# esphaptc.net
KiCad netlist of a schematic drawn in EasyEDA
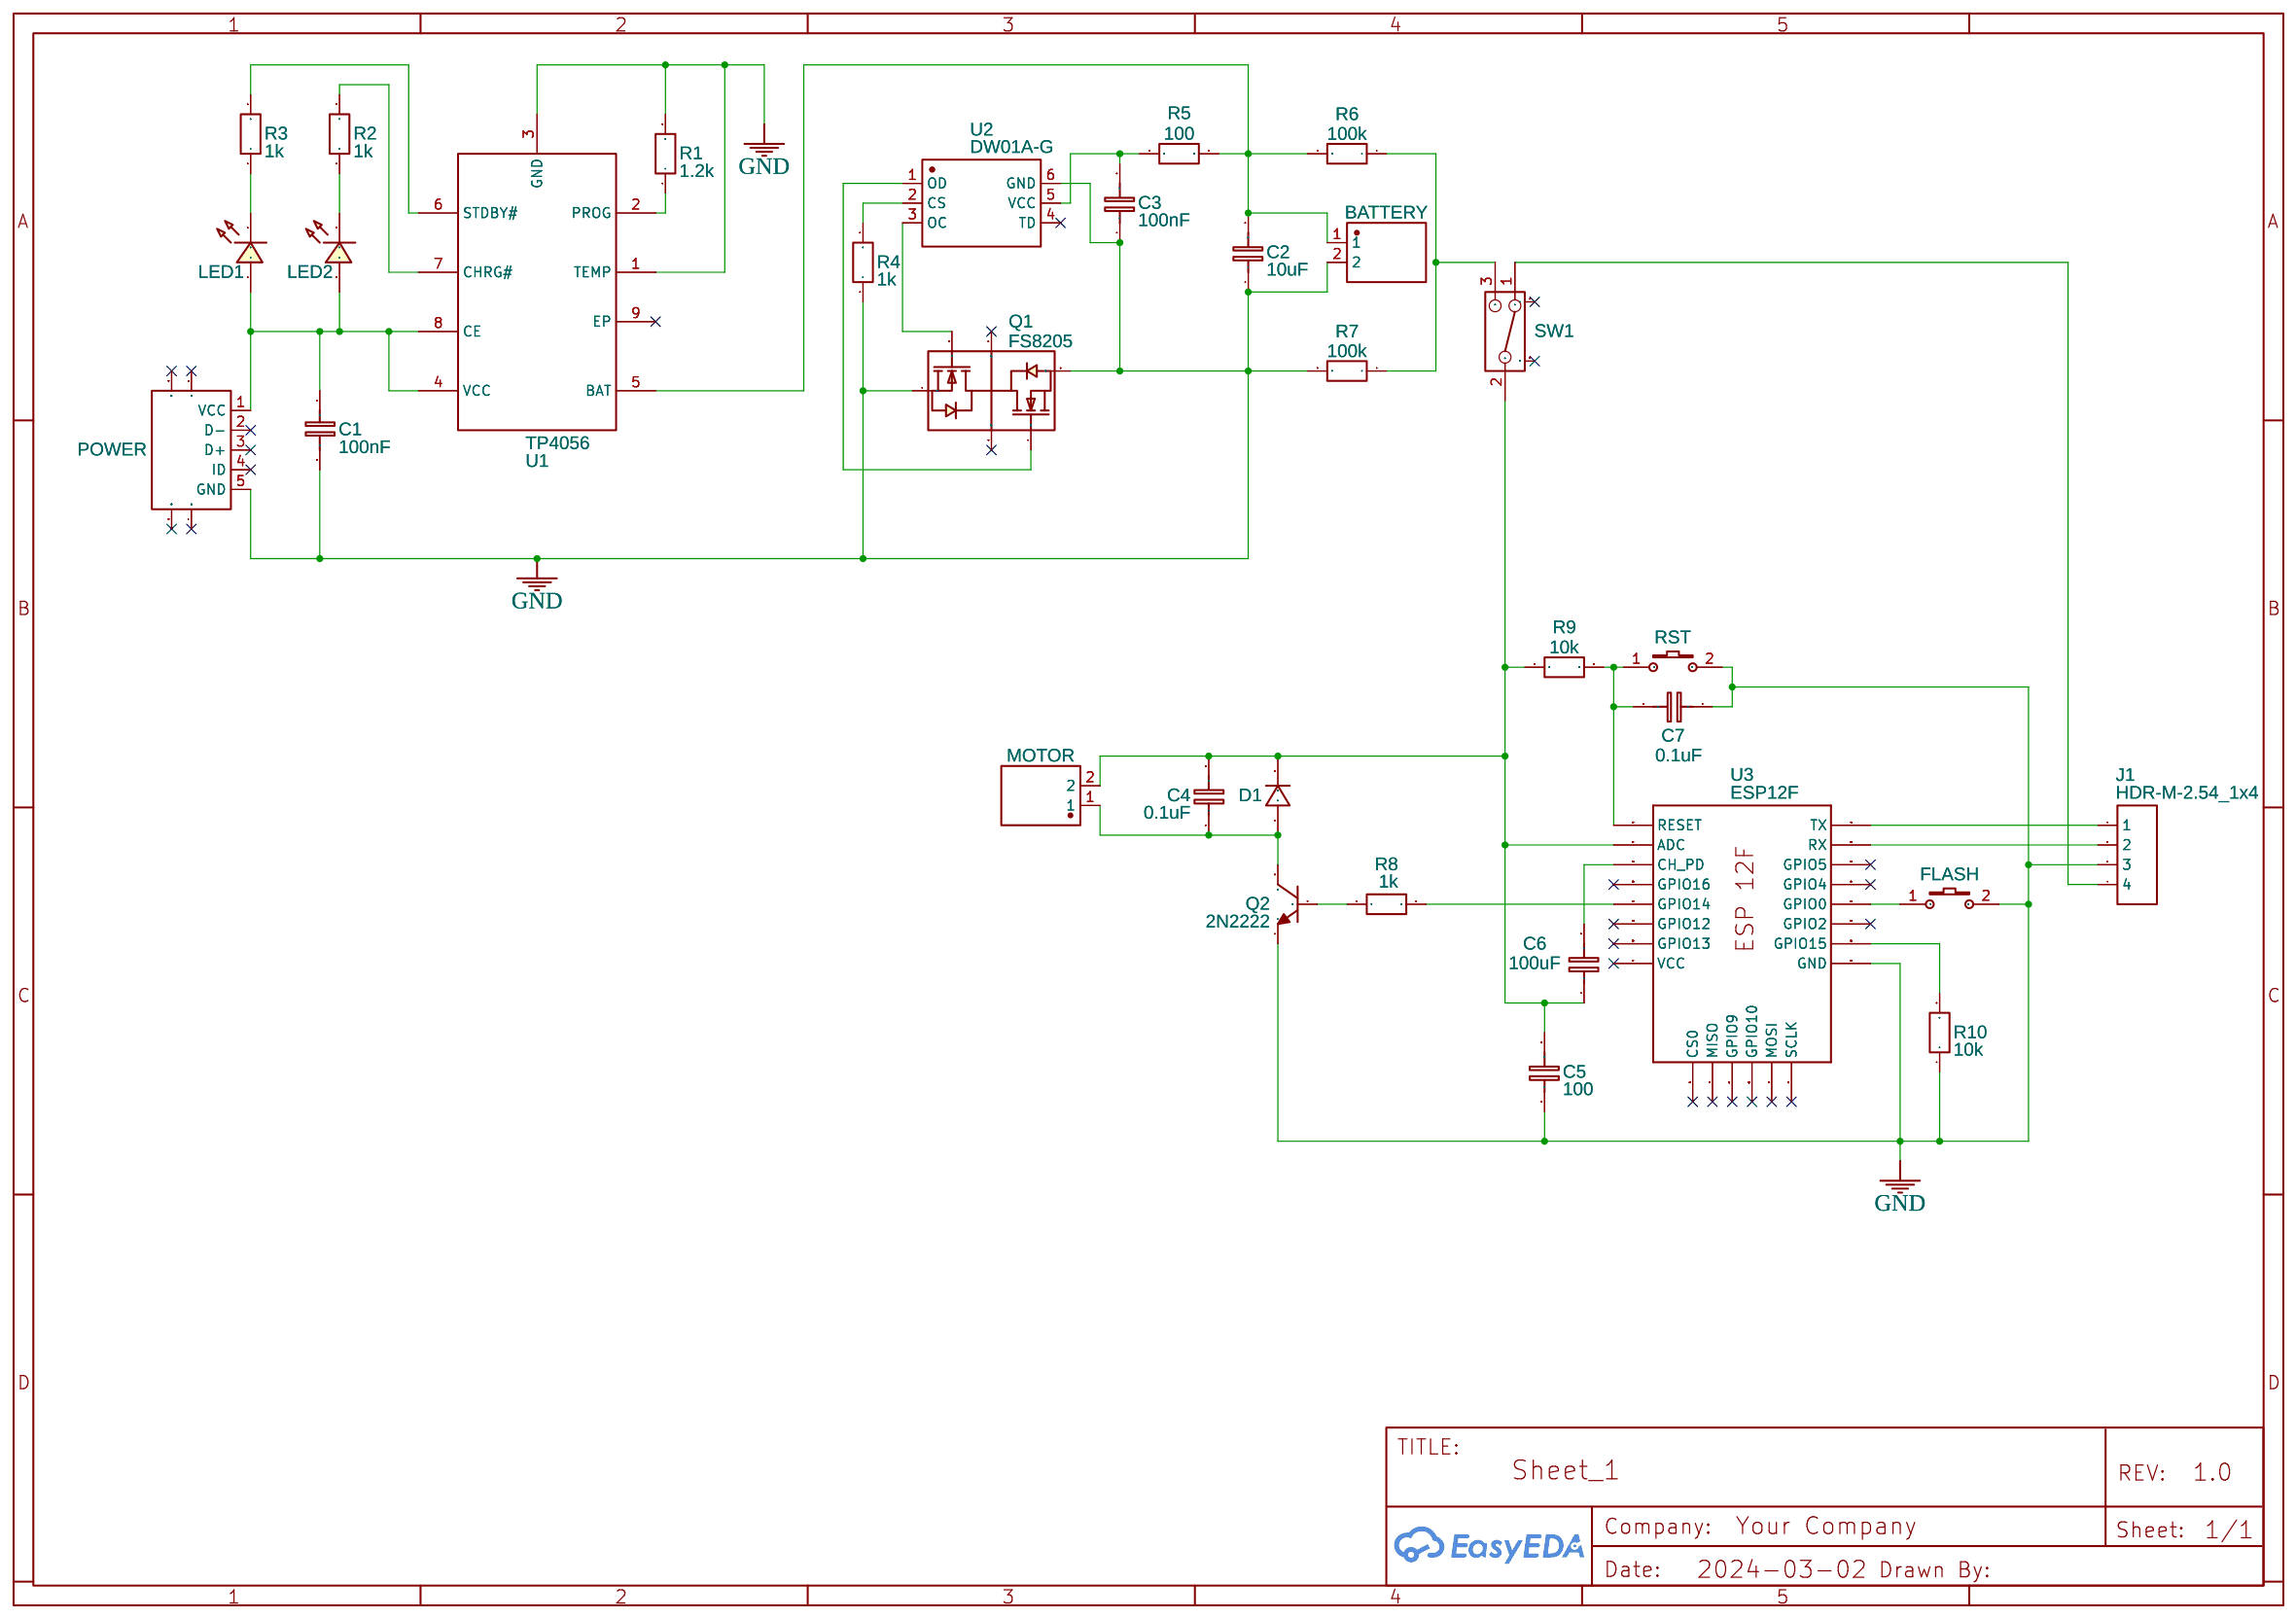
[diagram p0: schematic sheet]

(export (version "E")
  (design (tool "Eeschema 10.0.6"))
  (components
    (comp (ref "BATTERY")
      (value "B02B-XASK-1-A(LF)(SN)")
      (fields (field (name "Manufacturer") "JST"))
      (libsource (lib "") (part "B02B-XASK-1-A(LF)(SN)_1"))
    )
    (comp (ref "C1") (value "100nF") (libsource (lib "") (part "C_0603_EU_2")))
    (comp (ref "C2") (value "10uF") (libsource (lib "") (part "C_0603_EU_3")))
    (comp (ref "C3") (value "100nF") (libsource (lib "") (part "C_0603_EU_3")))
    (comp (ref "C4") (value "0.1uF") (libsource (lib "") (part "C_0603_EU_1")))
    (comp (ref "C5") (value "100") (libsource (lib "") (part "C_0603_EU")))
    (comp (ref "C6") (value "100uF") (libsource (lib "") (part "C_0603_EU")))
    (comp (ref "C7") (value "0.1uF") (libsource (lib "") (part "C_0603_EU_4")))
    (comp (ref "D1")
      (value "1N4007W")
      (fields (field (name "Manufacturer") "BLUE ROCKET"))
      (libsource (lib "") (part "1N4007W"))
    )
    (comp (ref "FLASH")
      (value "K2-3.6×6.1_SMD")
      (fields (field (name "Manufacturer Part") "K2-1107ST-A4SW-06"))
      (libsource (lib "") (part "K2-3.6×6.1_SMD"))
    )
    (comp (ref "J1") (value "HDR-M-2.54_1x4") (libsource (lib "") (part "HDR-M-2.54_1x4")))
    (comp (ref "LED1")
      (value "LED-0603_R")
      (fields
        (field (name "Manufacturer Part") "19-217/R6C-AL1M2VY/3T")
        (field (name "Manufacturer") "EVERLIGHT(台湾亿光)")
      )
      (libsource (lib "") (part "LED-0603_R"))
    )
    (comp (ref "LED2")
      (value "LED-0603_B")
      (fields
        (field (name "Manufacturer Part") "19-217/BHC-ZL1M2RY/3T")
        (field (name "Manufacturer") "EVERLIGHT(台湾亿光)")
      )
      (libsource (lib "") (part "LED-0603_B"))
    )
    (comp (ref "MOTOR")
      (value "B02B-XASK-1-A(LF)(SN)")
      (fields (field (name "Manufacturer") "JST"))
      (libsource (lib "") (part "B02B-XASK-1-A(LF)(SN)"))
    )
    (comp (ref "POWER")
      (value "USB-Micro_2")
      (fields (field (name "Manufacturer") "ValuePro"))
      (libsource (lib "") (part "USB-Micro_2"))
    )
    (comp (ref "Q1")
      (value "FS8205")
      (fields (field (name "Manufacturer") "FORTUNE(富晶)"))
      (libsource (lib "") (part "FS8205"))
    )
    (comp (ref "Q2")
      (value "2N2222")
      (fields (field (name "Manufacturer Part") "2n3904S-RTK/PS") (field (name "Manufacturer") "KEC"))
      (libsource (lib "") (part "2N3904(SOT-23)"))
    )
    (comp (ref "R1") (value "1.2k") (libsource (lib "") (part "R_0603_EU_2")))
    (comp (ref "R2") (value "1k") (libsource (lib "") (part "R_0603_EU_2")))
    (comp (ref "R3") (value "1k") (libsource (lib "") (part "R_0603_EU_2")))
    (comp (ref "R4") (value "1k") (libsource (lib "") (part "R_0603_EU_2")))
    (comp (ref "R5") (value "100") (libsource (lib "") (part "R_0603_EU_1")))
    (comp (ref "R6") (value "100k") (libsource (lib "") (part "R_0603_EU")))
    (comp (ref "R7") (value "100k") (libsource (lib "") (part "R_0603_EU")))
    (comp (ref "R8") (value "1k") (libsource (lib "") (part "R_0603_EU")))
    (comp (ref "R9") (value "10k") (libsource (lib "") (part "R_0603_EU_1")))
    (comp (ref "R10") (value "10k") (libsource (lib "") (part "R_0603_EU_2")))
    (comp (ref "RST")
      (value "K2-3.6×6.1_SMD")
      (fields (field (name "Manufacturer Part") "K2-1107ST-A4SW-06"))
      (libsource (lib "") (part "K2-3.6×6.1_SMD_1"))
    )
    (comp (ref "SW1")
      (value "SK-12D02-VG5")
      (fields (field (name "Manufacturer") "Rectangular Connectors - Contacts"))
      (libsource (lib "") (part "SK-12D02-VG5"))
    )
    (comp (ref "U1")
      (value "TP4056")
      (fields
        (field (name "Manufacturer Part") "TP4056-42-ESOP8")
        (field (name "Manufacturer") "TOPPOWER(南京拓微)")
      )
      (libsource (lib "") (part "TP4056"))
    )
    (comp (ref "U2")
      (value "DW01A-G")
      (fields (field (name "Manufacturer") "FORTUNE(富晶)"))
      (libsource (lib "") (part "DW01A-G"))
    )
    (comp (ref "U3") (value "ESP12F") (libsource (lib "") (part "ESP12F")))
  )
  (nets
    (net (code "1") (name "GND") (class "Default")
      (node (ref "BATTERY") (pin "2") (pinfunction "2_2") (pintype "unspecified"))
      (node (ref "C1") (pin "2") (pinfunction "2_2") (pintype "unspecified"))
      (node (ref "C2") (pin "1") (pinfunction "1_1") (pintype "unspecified"))
      (node (ref "C3") (pin "1") (pinfunction "1_1") (pintype "unspecified"))
      (node (ref "C5") (pin "1") (pinfunction "1_1") (pintype "unspecified"))
      (node (ref "C7") (pin "1") (pinfunction "1_1") (pintype "unspecified"))
      (node (ref "FLASH") (pin "2") (pinfunction "2_2") (pintype "unspecified"))
      (node (ref "J1") (pin "3") (pinfunction "3_3") (pintype "unspecified"))
      (node (ref "POWER") (pin "5") (pinfunction "GND_5") (pintype "input"))
      (node (ref "Q1") (pin "1") (pinfunction "S1_1") (pintype "unspecified"))
      (node (ref "Q1") (pin "3") (pinfunction "S2_3") (pintype "unspecified"))
      (node (ref "Q2") (pin "1") (pinfunction "E_1") (pintype "input"))
      (node (ref "R1") (pin "2") (pinfunction "2_2") (pintype "unspecified"))
      (node (ref "R10") (pin "1") (pinfunction "1_1") (pintype "unspecified"))
      (node (ref "R4") (pin "1") (pinfunction "1_1") (pintype "unspecified"))
      (node (ref "R7") (pin "2") (pinfunction "2_2") (pintype "unspecified"))
      (node (ref "RST") (pin "2") (pinfunction "2_2") (pintype "unspecified"))
      (node (ref "U1") (pin "1") (pinfunction "TEMP_1") (pintype "unspecified"))
      (node (ref "U1") (pin "3") (pinfunction "GND_3") (pintype "unspecified"))
      (node (ref "U2") (pin "6") (pinfunction "GND_6") (pintype "unspecified"))
      (node (ref "U3") (pin "GND") (pinfunction "GND_GND") (pintype "bidirectional"))
    )
    (net (code "2") (name "Net-(C4-Pad2)") (class "Default")
      (node (ref "C4") (pin "2") (pinfunction "2_2") (pintype "unspecified"))
      (node (ref "C5") (pin "2") (pinfunction "2_2") (pintype "unspecified"))
      (node (ref "C6") (pin "1") (pinfunction "1_1") (pintype "unspecified"))
      (node (ref "D1") (pin "1") (pinfunction "1_1") (pintype "unspecified"))
      (node (ref "MOTOR") (pin "2") (pinfunction "2_2") (pintype "unspecified"))
      (node (ref "R9") (pin "1") (pinfunction "1_1") (pintype "unspecified"))
      (node (ref "SW1") (pin "2") (pinfunction "2_2") (pintype "unspecified"))
      (node (ref "U3") (pin "ADC") (pinfunction "ADC_ADC") (pintype "bidirectional"))
    )
    (net (code "3") (name "Net-(C6-Pad2)") (class "Default")
      (node (ref "C6") (pin "2") (pinfunction "2_2") (pintype "unspecified"))
      (node (ref "U3") (pin "CH_PD") (pinfunction "CH_PD_CH_PD") (pintype "bidirectional"))
    )
    (net (code "4") (name "Net-(C7-Pad2)") (class "Default")
      (node (ref "C7") (pin "2") (pinfunction "2_2") (pintype "unspecified"))
      (node (ref "R9") (pin "2") (pinfunction "2_2") (pintype "unspecified"))
      (node (ref "RST") (pin "1") (pinfunction "1_1") (pintype "unspecified"))
      (node (ref "U3") (pin "RESET") (pinfunction "RESET_RESET") (pintype "bidirectional"))
    )
    (net (code "5") (name "Net-(FLASH-Pad1)") (class "Default")
      (node (ref "FLASH") (pin "1") (pinfunction "1_1") (pintype "unspecified"))
      (node (ref "U3") (pin "GPIO0") (pinfunction "GPIO0_GPIO0") (pintype "bidirectional"))
    )
    (net (code "6") (name "Net-(J1-Pad4)") (class "Default")
      (node (ref "J1") (pin "4") (pinfunction "4_4") (pintype "unspecified"))
      (node (ref "SW1") (pin "1") (pinfunction "1_1") (pintype "unspecified"))
    )
    (net (code "7") (name "Net-(LED1-Pad2)") (class "Default")
      (node (ref "LED1") (pin "2") (pinfunction "2_2") (pintype "unspecified"))
      (node (ref "R3") (pin "1") (pinfunction "1_1") (pintype "unspecified"))
    )
    (net (code "8") (name "Net-(LED2-Pad2)") (class "Default")
      (node (ref "LED2") (pin "2") (pinfunction "2_2") (pintype "unspecified"))
      (node (ref "R2") (pin "1") (pinfunction "1_1") (pintype "unspecified"))
    )
    (net (code "9") (name "Net-(POWER-VCC)") (class "Default")
      (node (ref "C1") (pin "1") (pinfunction "1_1") (pintype "unspecified"))
      (node (ref "LED1") (pin "1") (pinfunction "1_1") (pintype "unspecified"))
      (node (ref "LED2") (pin "1") (pinfunction "1_1") (pintype "unspecified"))
      (node (ref "POWER") (pin "1") (pinfunction "VCC_1") (pintype "input"))
      (node (ref "U1") (pin "4") (pinfunction "VCC_4") (pintype "unspecified"))
      (node (ref "U1") (pin "8") (pinfunction "CE_8") (pintype "unspecified"))
    )
    (net (code "10") (name "Net-(Q1-G1)") (class "Default")
      (node (ref "Q1") (pin "6") (pinfunction "G1_6") (pintype "unspecified"))
      (node (ref "U2") (pin "3") (pinfunction "OC_3") (pintype "unspecified"))
    )
    (net (code "11") (name "Net-(Q1-G2)") (class "Default")
      (node (ref "Q1") (pin "4") (pinfunction "G2_4") (pintype "unspecified"))
      (node (ref "U2") (pin "1") (pinfunction "OD_1") (pintype "unspecified"))
    )
    (net (code "12") (name "Net-(Q2-B)") (class "Default")
      (node (ref "Q2") (pin "2") (pinfunction "B_2") (pintype "input"))
      (node (ref "R8") (pin "2") (pinfunction "2_2") (pintype "unspecified"))
    )
    (net (code "13") (name "Net-(Q2-C)") (class "Default")
      (node (ref "C4") (pin "1") (pinfunction "1_1") (pintype "unspecified"))
      (node (ref "D1") (pin "2") (pinfunction "2_2") (pintype "unspecified"))
      (node (ref "MOTOR") (pin "1") (pinfunction "1_1") (pintype "unspecified"))
      (node (ref "Q2") (pin "3") (pinfunction "C_3") (pintype "input"))
    )
    (net (code "14") (name "Net-(R6-Pad1)") (class "Default")
      (node (ref "R6") (pin "1") (pinfunction "1_1") (pintype "unspecified"))
      (node (ref "R7") (pin "1") (pinfunction "1_1") (pintype "unspecified"))
      (node (ref "SW1") (pin "3") (pinfunction "3_3") (pintype "unspecified"))
    )
    (net (code "15") (name "Net-(R8-Pad1)") (class "Default")
      (node (ref "R8") (pin "1") (pinfunction "1_1") (pintype "unspecified"))
      (node (ref "U3") (pin "GPIO14") (pinfunction "GPIO14_GPIO14") (pintype "bidirectional"))
    )
    (net (code "16") (name "Net-(R10-Pad2)") (class "Default")
      (node (ref "R10") (pin "2") (pinfunction "2_2") (pintype "unspecified"))
      (node (ref "U3") (pin "GPIO15") (pinfunction "GPIO15_GPIO15") (pintype "bidirectional"))
    )
    (net (code "17") (name "Net-(U1-BAT)") (class "Default")
      (node (ref "BATTERY") (pin "1") (pinfunction "1_1") (pintype "unspecified"))
      (node (ref "C2") (pin "2") (pinfunction "2_2") (pintype "unspecified"))
      (node (ref "R5") (pin "2") (pinfunction "2_2") (pintype "unspecified"))
      (node (ref "R6") (pin "2") (pinfunction "2_2") (pintype "unspecified"))
      (node (ref "U1") (pin "5") (pinfunction "BAT_5") (pintype "unspecified"))
    )
    (net (code "18") (name "Net-(U1-CHRG#)") (class "Default")
      (node (ref "R2") (pin "2") (pinfunction "2_2") (pintype "unspecified"))
      (node (ref "U1") (pin "7") (pinfunction "CHRG#_7") (pintype "unspecified"))
    )
    (net (code "19") (name "Net-(U1-PROG)") (class "Default")
      (node (ref "R1") (pin "1") (pinfunction "1_1") (pintype "unspecified"))
      (node (ref "U1") (pin "2") (pinfunction "PROG_2") (pintype "unspecified"))
    )
    (net (code "20") (name "Net-(U1-STDBY#)") (class "Default")
      (node (ref "R3") (pin "2") (pinfunction "2_2") (pintype "unspecified"))
      (node (ref "U1") (pin "6") (pinfunction "STDBY#_6") (pintype "unspecified"))
    )
    (net (code "21") (name "Net-(U2-CS)") (class "Default")
      (node (ref "R4") (pin "2") (pinfunction "2_2") (pintype "unspecified"))
      (node (ref "U2") (pin "2") (pinfunction "CS_2") (pintype "unspecified"))
    )
    (net (code "22") (name "Net-(U2-VCC)") (class "Default")
      (node (ref "C3") (pin "2") (pinfunction "2_2") (pintype "unspecified"))
      (node (ref "R5") (pin "1") (pinfunction "1_1") (pintype "unspecified"))
      (node (ref "U2") (pin "5") (pinfunction "VCC_5") (pintype "unspecified"))
    )
    (net (code "23") (name "Net-(U3-RX)") (class "Default")
      (node (ref "J1") (pin "2") (pinfunction "2_2") (pintype "unspecified"))
      (node (ref "U3") (pin "RXD0") (pinfunction "RX_RXD0") (pintype "bidirectional"))
    )
    (net (code "24") (name "Net-(U3-TX)") (class "Default")
      (node (ref "J1") (pin "1") (pinfunction "1_1") (pintype "unspecified"))
      (node (ref "U3") (pin "TXD0") (pinfunction "TX_TXD0") (pintype "bidirectional"))
    )
    (net (code "25") (name "unconnected-(POWER-D+-Pad3)") (class "Default")
      (node (ref "POWER") (pin "3") (pinfunction "D+_3") (pintype "input+no_connect"))
    )
    (net (code "26") (name "unconnected-(POWER-D--Pad2)") (class "Default")
      (node (ref "POWER") (pin "2") (pinfunction "D-_2") (pintype "input+no_connect"))
    )
    (net (code "27") (name "unconnected-(POWER-ID-Pad4)") (class "Default")
      (node (ref "POWER") (pin "4") (pinfunction "ID_4") (pintype "input+no_connect"))
    )
    (net (code "28") (name "unconnected-(POWER-SH1-Pad8)") (class "Default")
      (node (ref "POWER") (pin "8") (pinfunction "SH1_8") (pintype "unspecified+no_connect"))
    )
    (net (code "29") (name "unconnected-(POWER-SH2-Pad9)") (class "Default")
      (node (ref "POWER") (pin "9") (pinfunction "SH2_9") (pintype "unspecified+no_connect"))
    )
    (net (code "30") (name "unconnected-(POWER-SH3-Pad6)") (class "Default")
      (node (ref "POWER") (pin "6") (pinfunction "SH3_6") (pintype "unspecified+no_connect"))
    )
    (net (code "31") (name "unconnected-(POWER-SH4-Pad7)") (class "Default")
      (node (ref "POWER") (pin "7") (pinfunction "SH4_7") (pintype "unspecified+no_connect"))
    )
    (net (code "32") (name "unconnected-(Q1-D12-Pad2)") (class "Default")
      (node (ref "Q1") (pin "2") (pinfunction "D12_2") (pintype "unspecified+no_connect"))
    )
    (net (code "33") (name "unconnected-(Q1-D12-Pad5)") (class "Default")
      (node (ref "Q1") (pin "5") (pinfunction "D12_5") (pintype "unspecified+no_connect"))
    )
    (net (code "34") (name "unconnected-(SW1-Pad4)") (class "Default")
      (node (ref "SW1") (pin "4") (pinfunction "4_4") (pintype "unspecified+no_connect"))
    )
    (net (code "35") (name "unconnected-(SW1-Pad5)") (class "Default")
      (node (ref "SW1") (pin "5") (pinfunction "5_5") (pintype "unspecified+no_connect"))
    )
    (net (code "36") (name "unconnected-(U1-EP-Pad9)") (class "Default")
      (node (ref "U1") (pin "9") (pinfunction "EP_9") (pintype "unspecified+no_connect"))
    )
    (net (code "37") (name "unconnected-(U2-TD-Pad4)") (class "Default")
      (node (ref "U2") (pin "4") (pinfunction "TD_4") (pintype "unspecified+no_connect"))
    )
    (net (code "38") (name "unconnected-(U3-PadCS0)") (class "Default")
      (node (ref "U3") (pin "CS0") (pinfunction "CS0_CS0") (pintype "bidirectional+no_connect"))
    )
    (net (code "39") (name "unconnected-(U3-PadGPIO2)") (class "Default")
      (node (ref "U3") (pin "GPIO2") (pinfunction "GPIO2_GPIO2") (pintype "bidirectional+no_connect"))
    )
    (net (code "40") (name "unconnected-(U3-PadGPIO4)") (class "Default")
      (node (ref "U3") (pin "GPIO4") (pinfunction "GPIO4_GPIO4") (pintype "bidirectional+no_connect"))
    )
    (net (code "41") (name "unconnected-(U3-PadGPIO5)") (class "Default")
      (node (ref "U3") (pin "GPIO5") (pinfunction "GPIO5_GPIO5") (pintype "bidirectional+no_connect"))
    )
    (net (code "42") (name "unconnected-(U3-PadGPIO9)") (class "Default")
      (node (ref "U3") (pin "GPIO9") (pinfunction "GPIO9_GPIO9") (pintype "bidirectional+no_connect"))
    )
    (net (code "43") (name "unconnected-(U3-PadGPIO10)") (class "Default")
      (node (ref "U3") (pin "GPIO10") (pinfunction "GPIO10_GPIO10") (pintype "bidirectional+no_connect"))
    )
    (net (code "44") (name "unconnected-(U3-PadGPIO12)") (class "Default")
      (node (ref "U3") (pin "GPIO12") (pinfunction "GPIO12_GPIO12") (pintype "bidirectional+no_connect"))
    )
    (net (code "45") (name "unconnected-(U3-PadGPIO13)") (class "Default")
      (node (ref "U3") (pin "GPIO13") (pinfunction "GPIO13_GPIO13") (pintype "bidirectional+no_connect"))
    )
    (net (code "46") (name "unconnected-(U3-PadGPIO16)") (class "Default")
      (node (ref "U3") (pin "GPIO16") (pinfunction "GPIO16_GPIO16") (pintype "bidirectional+no_connect"))
    )
    (net (code "47") (name "unconnected-(U3-PadMISO)") (class "Default")
      (node (ref "U3") (pin "MISO") (pinfunction "MISO_MISO") (pintype "bidirectional+no_connect"))
    )
    (net (code "48") (name "unconnected-(U3-PadMOSI)") (class "Default")
      (node (ref "U3") (pin "MOSI") (pinfunction "MOSI_MOSI") (pintype "bidirectional+no_connect"))
    )
    (net (code "49") (name "unconnected-(U3-PadSCLK)") (class "Default")
      (node (ref "U3") (pin "SCLK") (pinfunction "SCLK_SCLK") (pintype "bidirectional+no_connect"))
    )
    (net (code "50") (name "unconnected-(U3-PadVCC)") (class "Default")
      (node (ref "U3") (pin "VCC") (pinfunction "VCC_VCC") (pintype "bidirectional+no_connect"))
    )
  )
)
